# connectors.net
KiCad netlist of a schematic drawn in Altium Designer
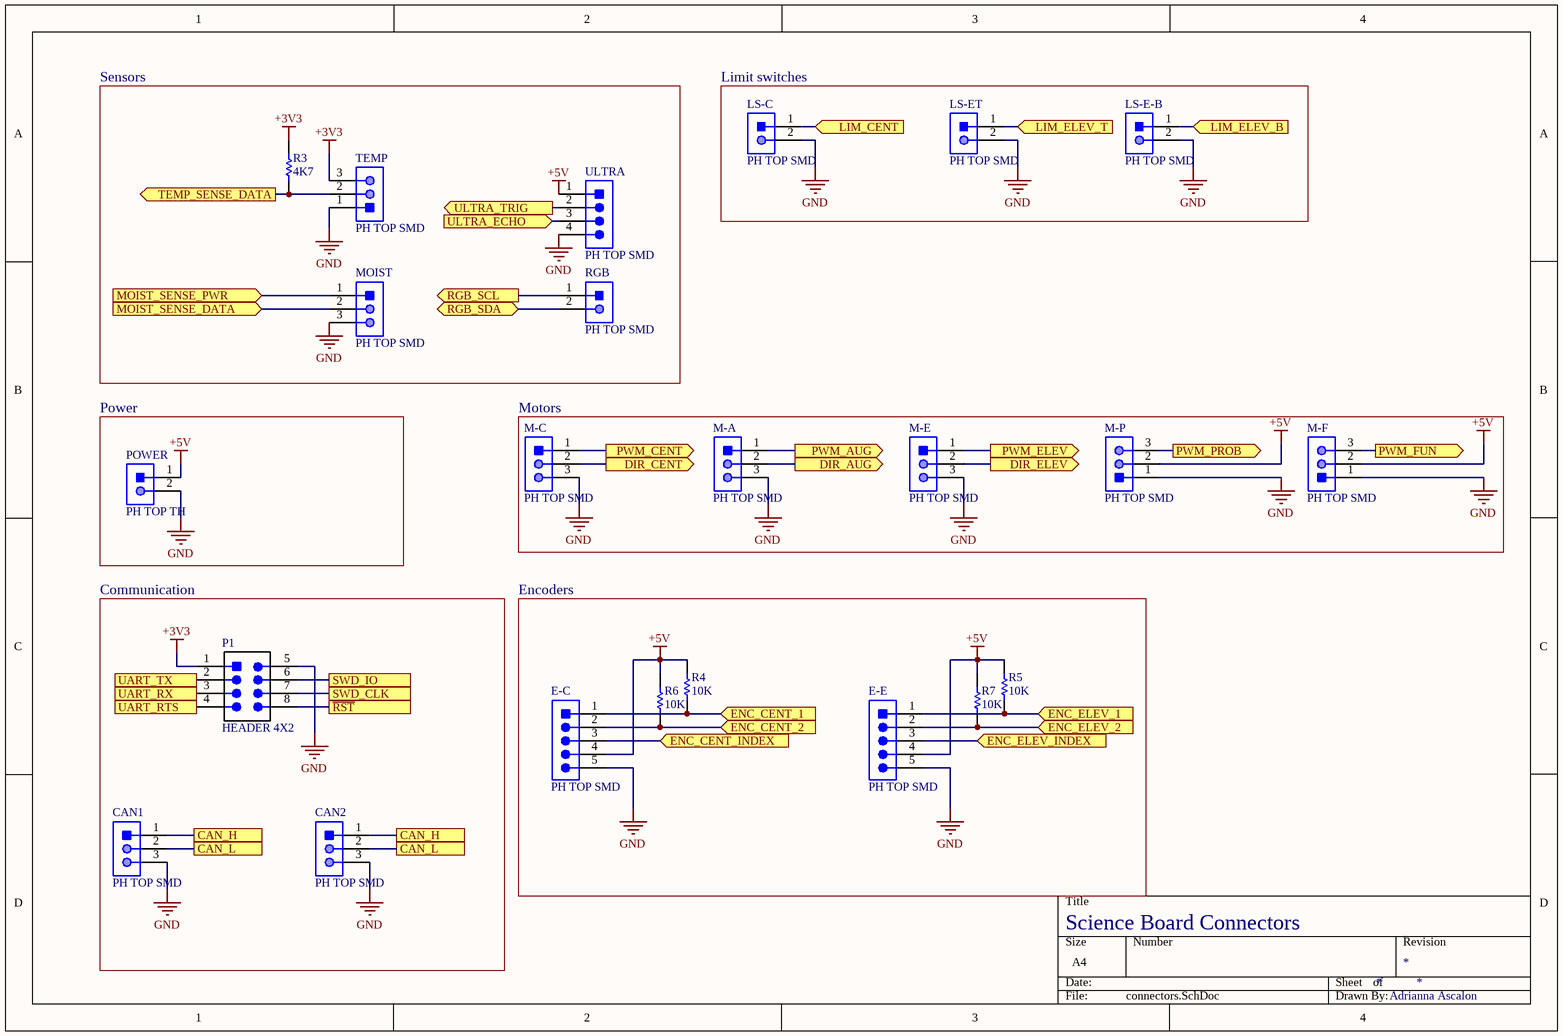
[diagram p0: connectors.SchDoc]

(export (version "E")
  (design (tool "Eeschema 10.0.6"))
  (components
    (comp (ref "CAN1")
      (value "PH TOP SMD")
      (footprint "JST-B3B-SM4-TB")
      (description "CONN HEADER PH TOP 3POS 2MM SMD")
      (fields (field (name "MANUFACTURER") "JST") (field (name "PART NUMBER") "B3B-PH-SM4-TB"))
      (libsource (lib "UWRT_Schematic_Library_2019") (part "CON_3M_PH_TOP_SMT"))
    )
    (comp (ref "CAN2")
      (value "PH TOP SMD")
      (footprint "JST-B3B-SM4-TB")
      (description "CONN HEADER PH TOP 3POS 2MM SMD")
      (fields (field (name "MANUFACTURER") "JST") (field (name "PART NUMBER") "B3B-PH-SM4-TB"))
      (libsource (lib "UWRT_Schematic_Library_2019") (part "CON_3M_PH_TOP_SMT"))
    )
    (comp (ref "E-C")
      (value "PH TOP SMD")
      (footprint "JST-B5B-SM4-TB")
      (description "CONN HEADER PH TOP 5POS 2MM SMD")
      (fields (field (name "MANUFACTURER") "JST") (field (name "PART NUMBER") "B5B-PH-SM4-TB"))
      (libsource (lib "UWRT_Schematic_Library_2019") (part "CON_5M_PH_TOP_SMT"))
    )
    (comp (ref "E-E")
      (value "PH TOP SMD")
      (footprint "JST-B5B-SM4-TB")
      (description "CONN HEADER PH TOP 5POS 2MM SMD")
      (fields (field (name "MANUFACTURER") "JST") (field (name "PART NUMBER") "B5B-PH-SM4-TB"))
      (libsource (lib "UWRT_Schematic_Library_2019") (part "CON_5M_PH_TOP_SMT"))
    )
    (comp (ref "LS-C")
      (value "PH TOP SMD")
      (footprint "JST-B2B-SM4-TB")
      (description "CONN HEADER PH TOP 2POS 2MM SMD")
      (fields (field (name "MANUFACTURER") "JST") (field (name "PART NUMBER") "B2B-PH-SM4-TB"))
      (libsource (lib "UWRT_Schematic_Library_2019") (part "CON_2M_PH_TOP_SMT"))
    )
    (comp (ref "LS-E-B")
      (value "PH TOP SMD")
      (footprint "JST-B2B-SM4-TB")
      (description "CONN HEADER PH TOP 2POS 2MM SMD")
      (fields (field (name "MANUFACTURER") "JST") (field (name "PART NUMBER") "B2B-PH-SM4-TB"))
      (libsource (lib "UWRT_Schematic_Library_2019") (part "CON_2M_PH_TOP_SMT"))
    )
    (comp (ref "LS-ET")
      (value "PH TOP SMD")
      (footprint "JST-B2B-SM4-TB")
      (description "CONN HEADER PH TOP 2POS 2MM SMD")
      (fields (field (name "MANUFACTURER") "JST") (field (name "PART NUMBER") "B2B-PH-SM4-TB"))
      (libsource (lib "UWRT_Schematic_Library_2019") (part "CON_2M_PH_TOP_SMT"))
    )
    (comp (ref "M-A")
      (value "PH TOP SMD")
      (footprint "JST-B3B-SM4-TB")
      (description "CONN HEADER PH TOP 3POS 2MM SMD")
      (fields (field (name "MANUFACTURER") "JST") (field (name "PART NUMBER") "B3B-PH-SM4-TB"))
      (libsource (lib "UWRT_Schematic_Library_2019") (part "CON_3M_PH_TOP_SMT"))
    )
    (comp (ref "M-C")
      (value "PH TOP SMD")
      (footprint "JST-B3B-SM4-TB")
      (description "CONN HEADER PH TOP 3POS 2MM SMD")
      (fields (field (name "MANUFACTURER") "JST") (field (name "PART NUMBER") "B3B-PH-SM4-TB"))
      (libsource (lib "UWRT_Schematic_Library_2019") (part "CON_3M_PH_TOP_SMT"))
    )
    (comp (ref "M-E")
      (value "PH TOP SMD")
      (footprint "JST-B3B-SM4-TB")
      (description "CONN HEADER PH TOP 3POS 2MM SMD")
      (fields (field (name "MANUFACTURER") "JST") (field (name "PART NUMBER") "B3B-PH-SM4-TB"))
      (libsource (lib "UWRT_Schematic_Library_2019") (part "CON_3M_PH_TOP_SMT"))
    )
    (comp (ref "M-F")
      (value "PH TOP SMD")
      (footprint "JST-B3B-SM4-TB")
      (description "CONN HEADER PH TOP 3POS 2MM SMD")
      (fields (field (name "MANUFACTURER") "JST") (field (name "PART NUMBER") "B3B-PH-SM4-TB"))
      (libsource (lib "") (part "CON_3M_PH_TOP_SMT_1"))
    )
    (comp (ref "M-P")
      (value "PH TOP SMD")
      (footprint "JST-B3B-SM4-TB")
      (description "CONN HEADER PH TOP 3POS 2MM SMD")
      (fields (field (name "MANUFACTURER") "JST") (field (name "PART NUMBER") "B3B-PH-SM4-TB"))
      (libsource (lib "") (part "CON_3M_PH_TOP_SMT_1"))
    )
    (comp (ref "MOIST")
      (value "PH TOP SMD")
      (footprint "JST-B3B-SM4-TB")
      (description "CONN HEADER PH TOP 3POS 2MM SMD")
      (fields (field (name "MANUFACTURER") "JST") (field (name "PART NUMBER") "B3B-PH-SM4-TB"))
      (libsource (lib "") (part "CON_3M_PH_TOP_SMT_2"))
    )
    (comp (ref "P1")
      (value "HEADER 4X2")
      (footprint "UWRT_Footprint_Library_2019:HEADER_2X4")
      (description "Header, 4-Pin Dual row")
      (fields (field (name "MPN") "GRPB042VWVN-RC") (field (name "DIGIKEY PART NUMBER") "S9015E-04-ND"))
      (libsource (lib "UWRT_Schematic_Library_2019") (part "HEADER 4X2"))
    )
    (comp (ref "POWER")
      (value "PH TOP TH")
      (footprint "JST-B2B-PHSK")
      (description "CONN HEADER PH TOP 2POS 2MM")
      (fields (field (name "MANUFACTURER") "JST") (field (name "PART NUMBER") "B2B-PH-K-S"))
      (libsource (lib "UWRT_Schematic_Library_2019") (part "CON_2M_PH_TOP_TH"))
    )
    (comp (ref "R3")
      (value "4K7")
      (footprint "RESC0603(1608)_N")
      (description "RES SMD 4.7K OHM 5% 1/10W 0603")
      (fields (field (name "MANUFACTURER") "Yageo") (field (name "TOLERANCE") "5%"))
      (libsource (lib "UWRT_Schematic_Library_2019") (part "RES_4K7_0603"))
    )
    (comp (ref "R4")
      (value "10K")
      (footprint "RESC0603(1608)_N")
      (description "RES SMD 10K OHM 5% 1/10W 0603")
      (fields (field (name "MANUFACTURER") "Yageo") (field (name "TOLERANCE") "5%"))
      (libsource (lib "UWRT_Schematic_Library_2019") (part "RES_10K_0603"))
    )
    (comp (ref "R5")
      (value "10K")
      (footprint "RESC0603(1608)_N")
      (description "RES SMD 10K OHM 5% 1/10W 0603")
      (fields (field (name "MANUFACTURER") "Yageo") (field (name "TOLERANCE") "5%"))
      (libsource (lib "UWRT_Schematic_Library_2019") (part "RES_10K_0603"))
    )
    (comp (ref "R6")
      (value "10K")
      (footprint "RESC0603(1608)_N")
      (description "RES SMD 10K OHM 5% 1/10W 0603")
      (fields (field (name "MANUFACTURER") "Yageo") (field (name "TOLERANCE") "5%"))
      (libsource (lib "UWRT_Schematic_Library_2019") (part "RES_10K_0603"))
    )
    (comp (ref "R7")
      (value "10K")
      (footprint "RESC0603(1608)_N")
      (description "RES SMD 10K OHM 5% 1/10W 0603")
      (fields (field (name "MANUFACTURER") "Yageo") (field (name "TOLERANCE") "5%"))
      (libsource (lib "UWRT_Schematic_Library_2019") (part "RES_10K_0603"))
    )
    (comp (ref "RGB")
      (value "PH TOP SMD")
      (footprint "JST-B2B-SM4-TB")
      (description "CONN HEADER PH TOP 2POS 2MM SMD")
      (fields (field (name "MANUFACTURER") "JST") (field (name "PART NUMBER") "B2B-PH-SM4-TB"))
      (libsource (lib "") (part "CON_2M_PH_TOP_SMT_1"))
    )
    (comp (ref "TEMP")
      (value "PH TOP SMD")
      (footprint "JST-B3B-SM4-TB")
      (description "CONN HEADER PH TOP 3POS 2MM SMD")
      (fields (field (name "MANUFACTURER") "JST") (field (name "PART NUMBER") "B3B-PH-SM4-TB"))
      (libsource (lib "") (part "CON_3M_PH_TOP_SMT_3"))
    )
    (comp (ref "ULTRA")
      (value "PH TOP SMD")
      (footprint "JST-B4B-SM4-TB")
      (description "CONN HEADER PH TOP 4POS 2MM SMD")
      (fields (field (name "MANUFACTURER") "JST") (field (name "PART NUMBER") "B4B-PH-SM4-TB"))
      (libsource (lib "UWRT_Schematic_Library_2019") (part "CON_4M_PH_TOP_SMT"))
    )
  )
  (nets
    (net (code "1") (name "+3V3") (class "Default")
      (node (ref "P1") (pin "1") (pinfunction "VCC_1") (pintype "passive"))
      (node (ref "R3") (pin "2") (pinfunction "2_2") (pintype "passive"))
      (node (ref "TEMP") (pin "3") (pinfunction "3_3") (pintype "passive"))
    )
    (net (code "2") (name "+5V") (class "Default")
      (node (ref "E-C") (pin "4") (pinfunction "4_4") (pintype "passive"))
      (node (ref "E-E") (pin "4") (pinfunction "4_4") (pintype "passive"))
      (node (ref "M-F") (pin "2") (pinfunction "2_2") (pintype "passive"))
      (node (ref "M-P") (pin "2") (pinfunction "2_2") (pintype "passive"))
      (node (ref "POWER") (pin "1") (pinfunction "1_1") (pintype "passive"))
      (node (ref "R4") (pin "2") (pinfunction "2_2") (pintype "passive"))
      (node (ref "R5") (pin "2") (pinfunction "2_2") (pintype "passive"))
      (node (ref "R6") (pin "2") (pinfunction "2_2") (pintype "passive"))
      (node (ref "R7") (pin "2") (pinfunction "2_2") (pintype "passive"))
      (node (ref "ULTRA") (pin "1") (pinfunction "1_1") (pintype "passive"))
    )
    (net (code "3") (name "/CAN_H") (class "Default")
      (node (ref "CAN1") (pin "1") (pinfunction "1_1") (pintype "passive"))
      (node (ref "CAN2") (pin "1") (pinfunction "1_1") (pintype "passive"))
    )
    (net (code "4") (name "/CAN_L") (class "Default")
      (node (ref "CAN1") (pin "2") (pinfunction "2_2") (pintype "passive"))
      (node (ref "CAN2") (pin "2") (pinfunction "2_2") (pintype "passive"))
    )
    (net (code "5") (name "/DIR_AUG") (class "Default")
      (node (ref "M-A") (pin "2") (pinfunction "2_2") (pintype "passive"))
    )
    (net (code "6") (name "/DIR_CENT") (class "Default")
      (node (ref "M-C") (pin "2") (pinfunction "2_2") (pintype "passive"))
    )
    (net (code "7") (name "/DIR_ELEV") (class "Default")
      (node (ref "M-E") (pin "2") (pinfunction "2_2") (pintype "passive"))
    )
    (net (code "8") (name "/ENC_CENT_1") (class "Default")
      (node (ref "E-C") (pin "1") (pinfunction "1_1") (pintype "passive"))
      (node (ref "R4") (pin "1") (pinfunction "1_1") (pintype "passive"))
    )
    (net (code "9") (name "/ENC_CENT_2") (class "Default")
      (node (ref "E-C") (pin "2") (pinfunction "2_2") (pintype "passive"))
      (node (ref "R6") (pin "1") (pinfunction "1_1") (pintype "passive"))
    )
    (net (code "10") (name "/ENC_CENT_INDEX") (class "Default")
      (node (ref "E-C") (pin "3") (pinfunction "3_3") (pintype "passive"))
    )
    (net (code "11") (name "/ENC_ELEV_1") (class "Default")
      (node (ref "E-E") (pin "1") (pinfunction "1_1") (pintype "passive"))
      (node (ref "R5") (pin "1") (pinfunction "1_1") (pintype "passive"))
    )
    (net (code "12") (name "/ENC_ELEV_2") (class "Default")
      (node (ref "E-E") (pin "2") (pinfunction "2_2") (pintype "passive"))
      (node (ref "R7") (pin "1") (pinfunction "1_1") (pintype "passive"))
    )
    (net (code "13") (name "/ENC_ELEV_INDEX") (class "Default")
      (node (ref "E-E") (pin "3") (pinfunction "3_3") (pintype "passive"))
    )
    (net (code "14") (name "/LIM_CENT") (class "Default")
      (node (ref "LS-C") (pin "1") (pinfunction "1_1") (pintype "passive"))
    )
    (net (code "15") (name "/LIM_ELEV_B") (class "Default")
      (node (ref "LS-E-B") (pin "1") (pinfunction "1_1") (pintype "passive"))
    )
    (net (code "16") (name "/LIM_ELEV_T") (class "Default")
      (node (ref "LS-ET") (pin "1") (pinfunction "1_1") (pintype "passive"))
    )
    (net (code "17") (name "/MOIST_SENSE_DATA") (class "Default")
      (node (ref "MOIST") (pin "2") (pinfunction "2_2") (pintype "passive"))
    )
    (net (code "18") (name "/MOIST_SENSE_PWR") (class "Default")
      (node (ref "MOIST") (pin "1") (pinfunction "1_1") (pintype "passive"))
    )
    (net (code "19") (name "/PWM_AUG") (class "Default")
      (node (ref "M-A") (pin "1") (pinfunction "1_1") (pintype "passive"))
    )
    (net (code "20") (name "/PWM_CENT") (class "Default")
      (node (ref "M-C") (pin "1") (pinfunction "1_1") (pintype "passive"))
    )
    (net (code "21") (name "/PWM_ELEV") (class "Default")
      (node (ref "M-E") (pin "1") (pinfunction "1_1") (pintype "passive"))
    )
    (net (code "22") (name "/PWM_FUN") (class "Default")
      (node (ref "M-F") (pin "3") (pinfunction "3_3") (pintype "passive"))
    )
    (net (code "23") (name "/PWM_PROB") (class "Default")
      (node (ref "M-P") (pin "3") (pinfunction "3_3") (pintype "passive"))
    )
    (net (code "24") (name "/RGB_SCL") (class "Default")
      (node (ref "RGB") (pin "1") (pinfunction "1_1") (pintype "passive"))
    )
    (net (code "25") (name "/RGB_SDA") (class "Default")
      (node (ref "RGB") (pin "2") (pinfunction "2_2") (pintype "passive"))
    )
    (net (code "26") (name "/SWD_CLK") (class "Default")
      (node (ref "P1") (pin "7") (pinfunction "3_7") (pintype "passive"))
    )
    (net (code "27") (name "/SWD_IO") (class "Default")
      (node (ref "P1") (pin "6") (pinfunction "2_6") (pintype "passive"))
    )
    (net (code "28") (name "/TEMP_SENSE_DATA") (class "Default")
      (node (ref "R3") (pin "1") (pinfunction "1_1") (pintype "passive"))
      (node (ref "TEMP") (pin "2") (pinfunction "2_2") (pintype "passive"))
    )
    (net (code "29") (name "/UART_RTS") (class "Default")
      (node (ref "P1") (pin "4") (pinfunction "4_4") (pintype "passive"))
    )
    (net (code "30") (name "/UART_RX") (class "Default")
      (node (ref "P1") (pin "3") (pinfunction "3_3") (pintype "passive"))
    )
    (net (code "31") (name "/UART_TX") (class "Default")
      (node (ref "P1") (pin "2") (pinfunction "2_2") (pintype "passive"))
    )
    (net (code "32") (name "/ULTRA_ECHO") (class "Default")
      (node (ref "ULTRA") (pin "3") (pinfunction "3_3") (pintype "passive"))
    )
    (net (code "33") (name "/ULTRA_TRIG") (class "Default")
      (node (ref "ULTRA") (pin "2") (pinfunction "2_2") (pintype "passive"))
    )
    (net (code "34") (name "/~{RST}") (class "Default")
      (node (ref "P1") (pin "8") (pinfunction "4_8") (pintype "passive"))
    )
    (net (code "35") (name "GND") (class "Default")
      (node (ref "CAN1") (pin "3") (pinfunction "3_3") (pintype "passive"))
      (node (ref "CAN2") (pin "3") (pinfunction "3_3") (pintype "passive"))
      (node (ref "E-C") (pin "5") (pinfunction "5_5") (pintype "passive"))
      (node (ref "E-E") (pin "5") (pinfunction "5_5") (pintype "passive"))
      (node (ref "LS-C") (pin "2") (pinfunction "2_2") (pintype "passive"))
      (node (ref "LS-E-B") (pin "2") (pinfunction "2_2") (pintype "passive"))
      (node (ref "LS-ET") (pin "2") (pinfunction "2_2") (pintype "passive"))
      (node (ref "M-A") (pin "3") (pinfunction "3_3") (pintype "passive"))
      (node (ref "M-C") (pin "3") (pinfunction "3_3") (pintype "passive"))
      (node (ref "M-E") (pin "3") (pinfunction "3_3") (pintype "passive"))
      (node (ref "M-F") (pin "1") (pinfunction "1_1") (pintype "passive"))
      (node (ref "M-P") (pin "1") (pinfunction "1_1") (pintype "passive"))
      (node (ref "MOIST") (pin "3") (pinfunction "3_3") (pintype "passive"))
      (node (ref "P1") (pin "5") (pinfunction "GND_5") (pintype "passive"))
      (node (ref "POWER") (pin "2") (pinfunction "2_2") (pintype "passive"))
      (node (ref "TEMP") (pin "1") (pinfunction "1_1") (pintype "passive"))
      (node (ref "ULTRA") (pin "4") (pinfunction "4_4") (pintype "passive"))
    )
  )
)
